# Mainboard.net
KiCad netlist of a schematic drawn in EAGLE
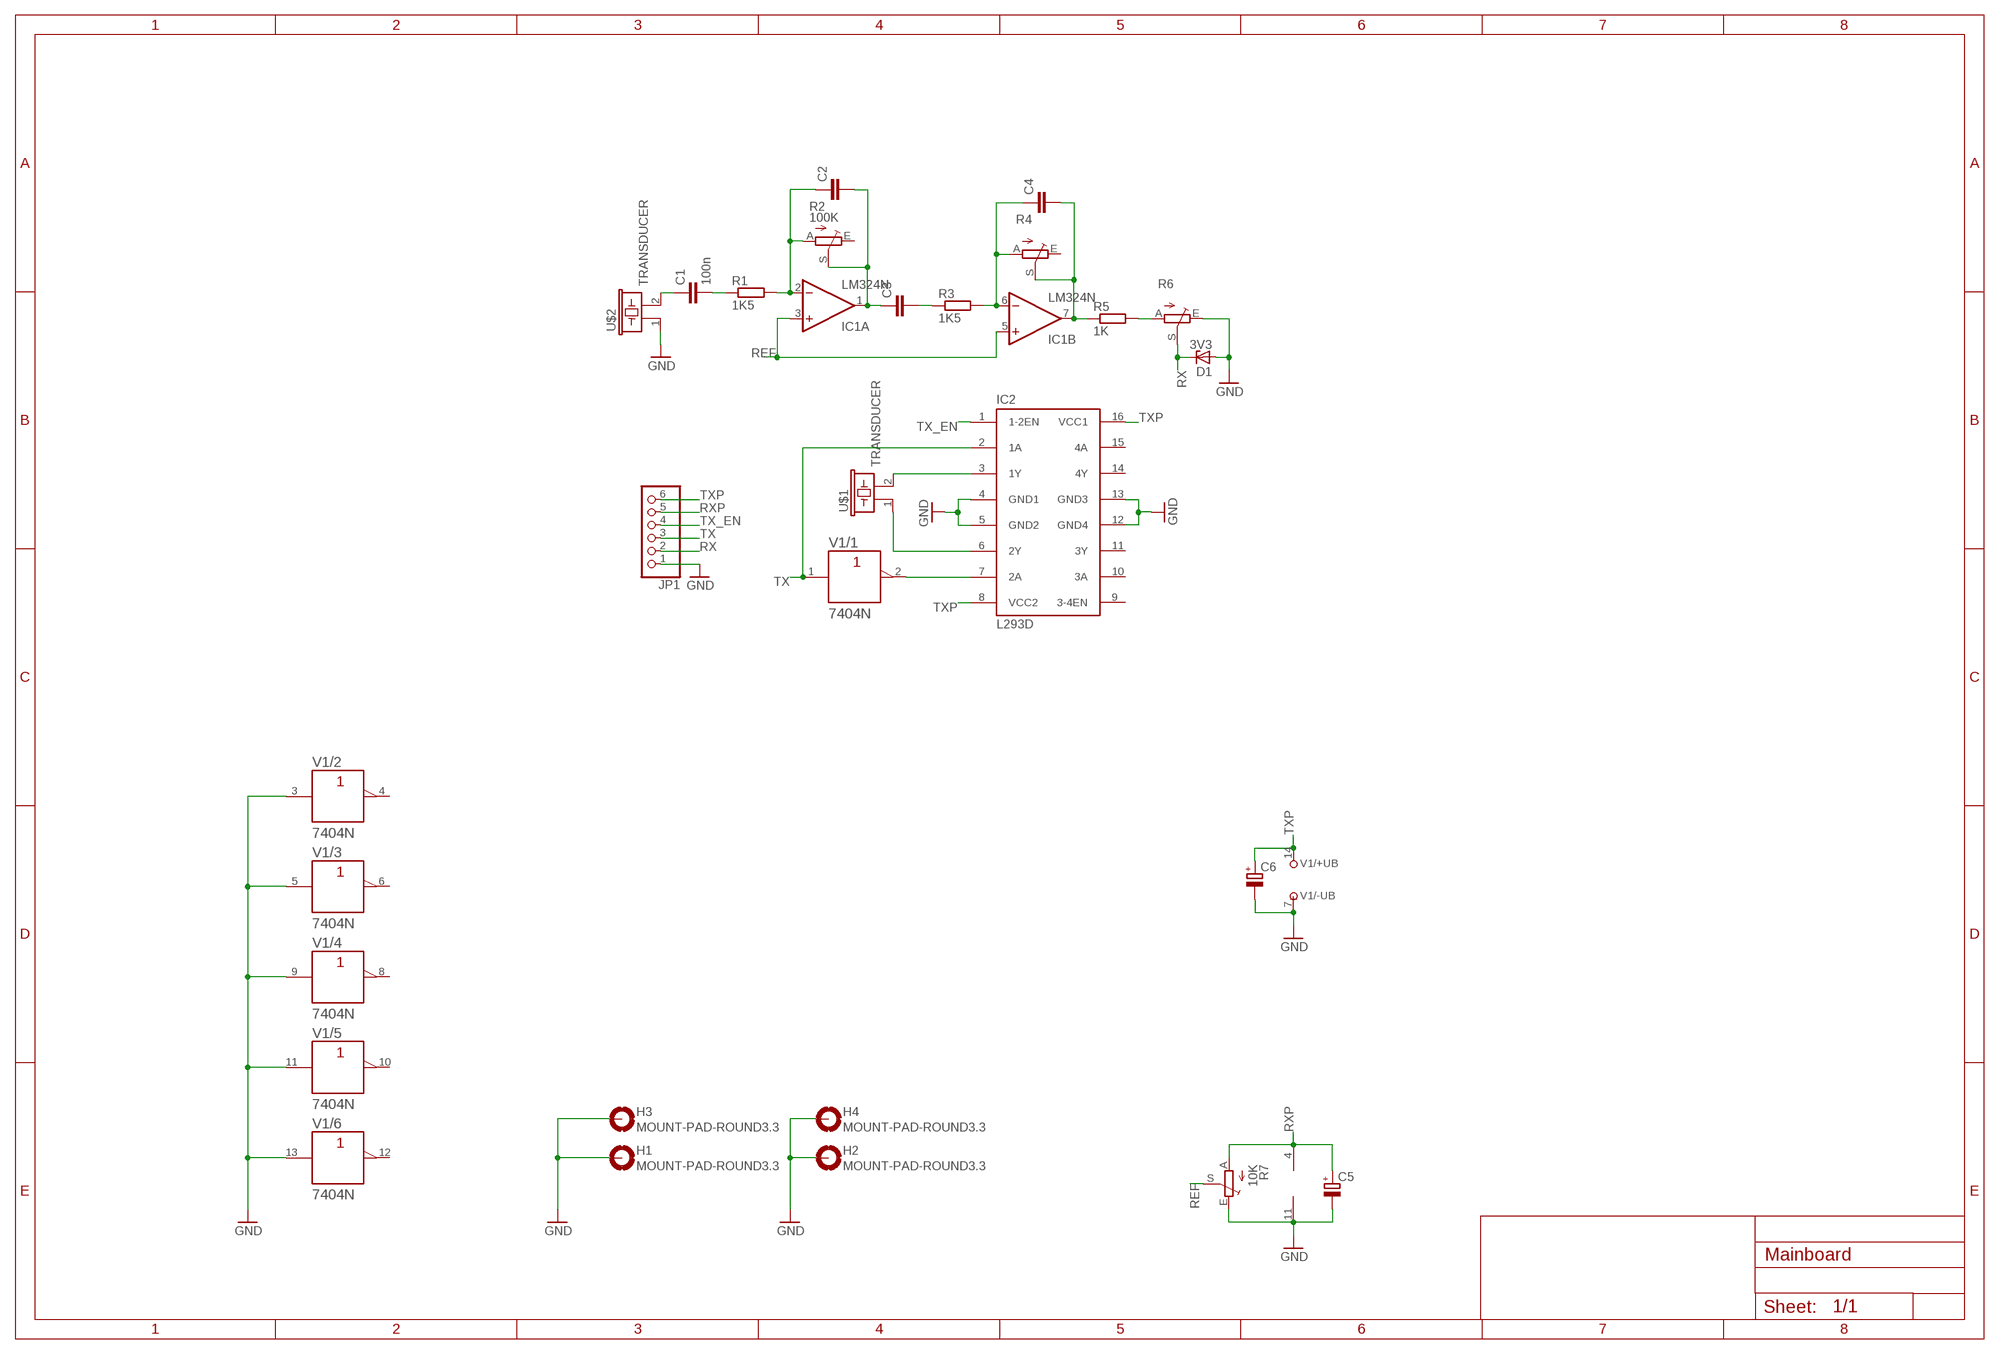
[diagram p0: schematic, sheet 1]

(export (version "E")
  (design (tool "Eeschema 10.0.6"))
  (components
    (comp (ref "C1")
      (value "100n")
      (footprint "eagle-import:C025-025X050")
      (libsource (lib "eagle-import") (part "C-EU025-025X050"))
    )
    (comp (ref "C2")
      (value "C-EU025-025X050")
      (footprint "eagle-import:C025-025X050")
      (libsource (lib "eagle-import") (part "C-EU025-025X050"))
    )
    (comp (ref "C3")
      (value "C-EU025-025X050")
      (footprint "eagle-import:C025-025X050")
      (libsource (lib "eagle-import") (part "C-EU025-025X050"))
    )
    (comp (ref "C4")
      (value "C-EU025-025X050")
      (footprint "eagle-import:C025-025X050")
      (libsource (lib "eagle-import") (part "C-EU025-025X050"))
    )
    (comp (ref "C5")
      (value "CPOL-EUE2-5")
      (footprint "eagle-import:E2-5")
      (libsource (lib "eagle-import") (part "CPOL-EUE2-5"))
    )
    (comp (ref "C6")
      (value "CPOL-EUE2-5")
      (footprint "eagle-import:E2-5")
      (libsource (lib "eagle-import") (part "CPOL-EUE2-5"))
    )
    (comp (ref "D1")
      (value "3V3")
      (footprint "eagle-import:ZDIO-2.5")
      (libsource (lib "eagle-import") (part "ZENER-DIODEZD-2.5"))
    )
    (comp (ref "H1")
      (value "MOUNT-PAD-ROUND3.3")
      (footprint "eagle-import:3,3-PAD")
      (libsource (lib "eagle-import") (part "MOUNT-PAD-ROUND3.3"))
    )
    (comp (ref "H2")
      (value "MOUNT-PAD-ROUND3.3")
      (footprint "eagle-import:3,3-PAD")
      (libsource (lib "eagle-import") (part "MOUNT-PAD-ROUND3.3"))
    )
    (comp (ref "H3")
      (value "MOUNT-PAD-ROUND3.3")
      (footprint "eagle-import:3,3-PAD")
      (libsource (lib "eagle-import") (part "MOUNT-PAD-ROUND3.3"))
    )
    (comp (ref "H4")
      (value "MOUNT-PAD-ROUND3.3")
      (footprint "eagle-import:3,3-PAD")
      (libsource (lib "eagle-import") (part "MOUNT-PAD-ROUND3.3"))
    )
    (comp (ref "IC1")
      (value "LM324N")
      (footprint "eagle-import:DIL14")
      (libsource (lib "eagle-import") (part "LM324N"))
    )
    (comp (ref "IC2")
      (value "L293D")
      (footprint "eagle-import:DIL16")
      (libsource (lib "eagle-import") (part "L293D"))
    )
    (comp (ref "JP1")
      (value "PINHD-1X6")
      (footprint "eagle-import:1X06")
      (libsource (lib "eagle-import") (part "PINHD-1X6"))
    )
    (comp (ref "R1")
      (value "1K5")
      (footprint "eagle-import:0207_2V")
      (libsource (lib "eagle-import") (part "R-EU_0207/2V"))
    )
    (comp (ref "R2")
      (value "100K")
      (footprint "eagle-import:S63P")
      (libsource (lib "eagle-import") (part "TRIM_EU-S63P"))
    )
    (comp (ref "R3")
      (value "1K5")
      (footprint "eagle-import:0207_2V")
      (libsource (lib "eagle-import") (part "R-EU_0207/2V"))
    )
    (comp (ref "R4")
      (value "TRIM_EU-S63P")
      (footprint "eagle-import:S63P")
      (libsource (lib "eagle-import") (part "TRIM_EU-S63P"))
    )
    (comp (ref "R5")
      (value "1K")
      (footprint "eagle-import:0207_2V")
      (libsource (lib "eagle-import") (part "R-EU_0207/2V"))
    )
    (comp (ref "R6")
      (value "TRIM_EU-S63P")
      (footprint "eagle-import:S63P")
      (libsource (lib "eagle-import") (part "TRIM_EU-S63P"))
    )
    (comp (ref "R7")
      (value "10K")
      (footprint "eagle-import:S63P")
      (libsource (lib "eagle-import") (part "TRIM_EU-S63P"))
    )
    (comp (ref "U$1")
      (value "TRANSDUCER")
      (footprint "eagle-import:TRANSDUCER")
      (libsource (lib "eagle-import") (part "TRANSDUCER"))
    )
    (comp (ref "U$2")
      (value "TRANSDUCER")
      (footprint "eagle-import:TRANSDUCER")
      (libsource (lib "eagle-import") (part "TRANSDUCER"))
    )
    (comp (ref "V1")
      (value "7404N")
      (footprint "eagle-import:DIL14")
      (libsource (lib "eagle-import") (part "7404N"))
    )
  )
  (nets
    (net (code "1") (name "/REF") (class "Default")
      (node (ref "IC1") (pin "3") (pinfunction "+IN_3") (pintype "input"))
      (node (ref "IC1") (pin "5") (pinfunction "+IN_5") (pintype "input"))
      (node (ref "R7") (pin "S") (pinfunction "S_S") (pintype "passive"))
    )
    (net (code "2") (name "/RX") (class "Default")
      (node (ref "D1") (pin "C") (pinfunction "C_C") (pintype "passive"))
      (node (ref "JP1") (pin "2") (pinfunction "2_2") (pintype "passive"))
      (node (ref "R6") (pin "S") (pinfunction "S_S") (pintype "passive"))
    )
    (net (code "3") (name "/RXP") (class "Default")
      (node (ref "C5") (pin "+") (pinfunction "+_+") (pintype "passive"))
      (node (ref "IC1") (pin "4") (pinfunction "V+_4") (pintype "power_in"))
      (node (ref "JP1") (pin "5") (pinfunction "5_5") (pintype "passive"))
      (node (ref "R7") (pin "A") (pinfunction "A_A") (pintype "passive"))
    )
    (net (code "4") (name "/TX") (class "Default")
      (node (ref "IC2") (pin "2") (pinfunction "1A_2") (pintype "input"))
      (node (ref "JP1") (pin "3") (pinfunction "3_3") (pintype "passive"))
      (node (ref "V1") (pin "1") (pinfunction "A_1") (pintype "input"))
    )
    (net (code "5") (name "/TXP") (class "Default")
      (node (ref "C6") (pin "+") (pinfunction "+_+") (pintype "passive"))
      (node (ref "IC2") (pin "16") (pinfunction "VCC1_16") (pintype "power_in"))
      (node (ref "IC2") (pin "8") (pinfunction "VCC2_8") (pintype "power_in"))
      (node (ref "JP1") (pin "6") (pinfunction "6_6") (pintype "passive"))
      (node (ref "V1") (pin "14") (pinfunction "+UB_14") (pintype "power_in"))
    )
    (net (code "6") (name "/TX_EN") (class "Default")
      (node (ref "IC2") (pin "1") (pinfunction "1-2EN_1") (pintype "input"))
      (node (ref "JP1") (pin "4") (pinfunction "4_4") (pintype "passive"))
    )
    (net (code "7") (name "GND") (class "Default")
      (node (ref "C5") (pin "-") (pinfunction "-_-") (pintype "passive"))
      (node (ref "C6") (pin "-") (pinfunction "-_-") (pintype "passive"))
      (node (ref "D1") (pin "A") (pinfunction "A_A") (pintype "passive"))
      (node (ref "H1") (pin "B3,3") (pinfunction "MOUNT_B3,3") (pintype "passive"))
      (node (ref "H2") (pin "B3,3") (pinfunction "MOUNT_B3,3") (pintype "passive"))
      (node (ref "H3") (pin "B3,3") (pinfunction "MOUNT_B3,3") (pintype "passive"))
      (node (ref "H4") (pin "B3,3") (pinfunction "MOUNT_B3,3") (pintype "passive"))
      (node (ref "IC1") (pin "11") (pinfunction "V-_11") (pintype "power_in"))
      (node (ref "IC2") (pin "12") (pinfunction "GND4_12") (pintype "power_in"))
      (node (ref "IC2") (pin "13") (pinfunction "GND3_13") (pintype "power_in"))
      (node (ref "IC2") (pin "4") (pinfunction "GND1_4") (pintype "power_in"))
      (node (ref "IC2") (pin "5") (pinfunction "GND2_5") (pintype "power_in"))
      (node (ref "JP1") (pin "1") (pinfunction "1_1") (pintype "passive"))
      (node (ref "R6") (pin "E") (pinfunction "E_E") (pintype "passive"))
      (node (ref "R7") (pin "E") (pinfunction "E_E") (pintype "passive"))
      (node (ref "U$2") (pin "1") (pinfunction "1_1") (pintype "passive"))
      (node (ref "V1") (pin "11") (pinfunction "A_11") (pintype "input"))
      (node (ref "V1") (pin "13") (pinfunction "A_13") (pintype "input"))
      (node (ref "V1") (pin "3") (pinfunction "A_3") (pintype "input"))
      (node (ref "V1") (pin "5") (pinfunction "A_5") (pintype "input"))
      (node (ref "V1") (pin "7") (pinfunction "-UB_7") (pintype "power_in"))
      (node (ref "V1") (pin "9") (pinfunction "A_9") (pintype "input"))
    )
    (net (code "8") (name "Net-(C1-Pad1)") (class "Default")
      (node (ref "C1") (pin "1") (pinfunction "1_1") (pintype "passive"))
      (node (ref "U$2") (pin "2") (pinfunction "2_2") (pintype "passive"))
    )
    (net (code "9") (name "Net-(C1-Pad2)") (class "Default")
      (node (ref "C1") (pin "2") (pinfunction "2_2") (pintype "passive"))
      (node (ref "R1") (pin "1") (pinfunction "1_1") (pintype "passive"))
    )
    (net (code "10") (name "Net-(C3-Pad2)") (class "Default")
      (node (ref "C3") (pin "2") (pinfunction "2_2") (pintype "passive"))
      (node (ref "R3") (pin "1") (pinfunction "1_1") (pintype "passive"))
    )
    (net (code "11") (name "Net-(IC1A--IN)") (class "Default")
      (node (ref "C2") (pin "1") (pinfunction "1_1") (pintype "passive"))
      (node (ref "IC1") (pin "2") (pinfunction "-IN_2") (pintype "input"))
      (node (ref "R1") (pin "2") (pinfunction "2_2") (pintype "passive"))
      (node (ref "R2") (pin "A") (pinfunction "A_A") (pintype "passive"))
    )
    (net (code "12") (name "Net-(IC1A-OUT)") (class "Default")
      (node (ref "C2") (pin "2") (pinfunction "2_2") (pintype "passive"))
      (node (ref "C3") (pin "1") (pinfunction "1_1") (pintype "passive"))
      (node (ref "IC1") (pin "1") (pinfunction "OUT_1") (pintype "output"))
      (node (ref "R2") (pin "S") (pinfunction "S_S") (pintype "passive"))
    )
    (net (code "13") (name "Net-(IC1B--IN)") (class "Default")
      (node (ref "C4") (pin "1") (pinfunction "1_1") (pintype "passive"))
      (node (ref "IC1") (pin "6") (pinfunction "-IN_6") (pintype "input"))
      (node (ref "R3") (pin "2") (pinfunction "2_2") (pintype "passive"))
      (node (ref "R4") (pin "A") (pinfunction "A_A") (pintype "passive"))
    )
    (net (code "14") (name "Net-(IC1B-OUT)") (class "Default")
      (node (ref "C4") (pin "2") (pinfunction "2_2") (pintype "passive"))
      (node (ref "IC1") (pin "7") (pinfunction "OUT_7") (pintype "output"))
      (node (ref "R4") (pin "S") (pinfunction "S_S") (pintype "passive"))
      (node (ref "R5") (pin "1") (pinfunction "1_1") (pintype "passive"))
    )
    (net (code "15") (name "Net-(IC2-1Y)") (class "Default")
      (node (ref "IC2") (pin "3") (pinfunction "1Y_3") (pintype "output"))
      (node (ref "U$1") (pin "2") (pinfunction "2_2") (pintype "passive"))
    )
    (net (code "16") (name "Net-(IC2-2A)") (class "Default")
      (node (ref "IC2") (pin "7") (pinfunction "2A_7") (pintype "input"))
      (node (ref "V1") (pin "2") (pinfunction "Y_2") (pintype "output"))
    )
    (net (code "17") (name "Net-(IC2-2Y)") (class "Default")
      (node (ref "IC2") (pin "6") (pinfunction "2Y_6") (pintype "output"))
      (node (ref "U$1") (pin "1") (pinfunction "1_1") (pintype "passive"))
    )
    (net (code "18") (name "Net-(R5-Pad2)") (class "Default")
      (node (ref "R5") (pin "2") (pinfunction "2_2") (pintype "passive"))
      (node (ref "R6") (pin "A") (pinfunction "A_A") (pintype "passive"))
    )
    (net (code "19") (name "unconnected-(IC2-3-4EN-Pad9)") (class "Default")
      (node (ref "IC2") (pin "9") (pinfunction "3-4EN_9") (pintype "input"))
    )
    (net (code "20") (name "unconnected-(IC2-3A-Pad10)") (class "Default")
      (node (ref "IC2") (pin "10") (pinfunction "3A_10") (pintype "input"))
    )
    (net (code "21") (name "unconnected-(IC2-3Y-Pad11)") (class "Default")
      (node (ref "IC2") (pin "11") (pinfunction "3Y_11") (pintype "output"))
    )
    (net (code "22") (name "unconnected-(IC2-4A-Pad15)") (class "Default")
      (node (ref "IC2") (pin "15") (pinfunction "4A_15") (pintype "input"))
    )
    (net (code "23") (name "unconnected-(IC2-4Y-Pad14)") (class "Default")
      (node (ref "IC2") (pin "14") (pinfunction "4Y_14") (pintype "output"))
    )
    (net (code "24") (name "unconnected-(R2-PadE)") (class "Default")
      (node (ref "R2") (pin "E") (pinfunction "E_E") (pintype "passive"))
    )
    (net (code "25") (name "unconnected-(R4-PadE)") (class "Default")
      (node (ref "R4") (pin "E") (pinfunction "E_E") (pintype "passive"))
    )
    (net (code "26") (name "unconnected-(V1D-Y-Pad4)") (class "Default")
      (node (ref "V1") (pin "4") (pinfunction "Y_4") (pintype "output"))
    )
    (net (code "27") (name "unconnected-(V1E-Y-Pad6)") (class "Default")
      (node (ref "V1") (pin "6") (pinfunction "Y_6") (pintype "output"))
    )
    (net (code "28") (name "unconnected-(V1F-Y-Pad8)") (class "Default")
      (node (ref "V1") (pin "8") (pinfunction "Y_8") (pintype "output"))
    )
    (net (code "29") (name "unconnected-(V1G-Y-Pad10)") (class "Default")
      (node (ref "V1") (pin "10") (pinfunction "Y_10") (pintype "output"))
    )
    (net (code "30") (name "unconnected-(V1H-Y-Pad12)") (class "Default")
      (node (ref "V1") (pin "12") (pinfunction "Y_12") (pintype "output"))
    )
  )
)
